# water.net
KiCad netlist of a schematic drawn in EAGLE
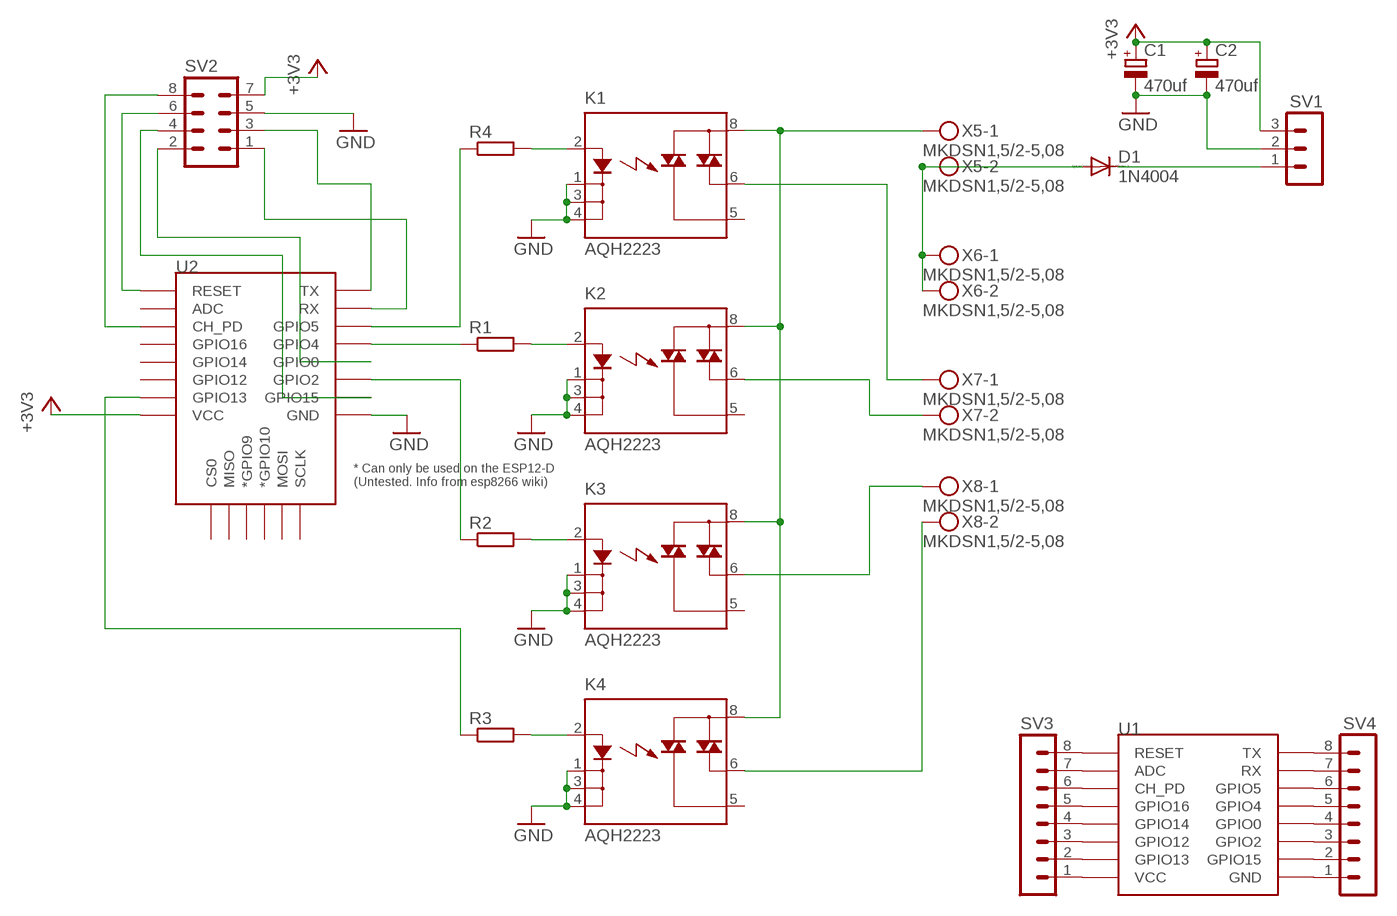
[diagram p0: schematic, sheet 1]

(export (version "E")
  (design (tool "Eeschema 10.0.6"))
  (components
    (comp (ref "C1")
      (value "470uf")
      (footprint "eagle-import:E5-10,5")
      (libsource (lib "eagle-import") (part "CPOL-EUE5-10.5"))
    )
    (comp (ref "C2")
      (value "470uf")
      (footprint "eagle-import:E5-10,5")
      (libsource (lib "eagle-import") (part "CPOL-EUE5-10.5"))
    )
    (comp (ref "D1")
      (value "1N4004")
      (footprint "eagle-import:DO41-10")
      (libsource (lib "eagle-import") (part "1N4004"))
    )
    (comp (ref "K1")
      (value "AQH2223")
      (footprint "eagle-import:DIL07")
      (fields (field (name "MF") "AROMAT/ MATSUSHITA"))
      (libsource (lib "eagle-import") (part "AQH2232"))
    )
    (comp (ref "K2")
      (value "AQH2223")
      (footprint "eagle-import:DIL07")
      (fields (field (name "MF") "AROMAT/ MATSUSHITA"))
      (libsource (lib "eagle-import") (part "AQH2232"))
    )
    (comp (ref "K3")
      (value "AQH2223")
      (footprint "eagle-import:DIL07")
      (fields (field (name "MF") "AROMAT/ MATSUSHITA"))
      (libsource (lib "eagle-import") (part "AQH2232"))
    )
    (comp (ref "K4")
      (value "AQH2223")
      (footprint "eagle-import:DIL07")
      (fields (field (name "MF") "AROMAT/ MATSUSHITA"))
      (libsource (lib "eagle-import") (part "AQH2232"))
    )
    (comp (ref "R1")
      (value "R-EU_R1206")
      (footprint "eagle-import:R1206")
      (libsource (lib "eagle-import") (part "R-EU_R1206"))
    )
    (comp (ref "R2")
      (value "R-EU_R1206")
      (footprint "eagle-import:R1206")
      (libsource (lib "eagle-import") (part "R-EU_R1206"))
    )
    (comp (ref "R3")
      (value "R-EU_R1206")
      (footprint "eagle-import:R1206")
      (libsource (lib "eagle-import") (part "R-EU_R1206"))
    )
    (comp (ref "R4")
      (value "R-EU_R1206")
      (footprint "eagle-import:R1206")
      (libsource (lib "eagle-import") (part "R-EU_R1206"))
    )
    (comp (ref "SV1")
      (value "MA03-1")
      (footprint "eagle-import:MA03-1")
      (libsource (lib "eagle-import") (part "MA03-1"))
    )
    (comp (ref "SV2")
      (value "MA04-2")
      (footprint "eagle-import:MA04-2")
      (libsource (lib "eagle-import") (part "MA04-2"))
    )
    (comp (ref "SV3")
      (value "MA08-1")
      (footprint "eagle-import:MA08-1")
      (libsource (lib "eagle-import") (part "MA08-1"))
    )
    (comp (ref "SV4")
      (value "MA08-1")
      (footprint "eagle-import:MA08-1")
      (libsource (lib "eagle-import") (part "MA08-1"))
    )
    (comp (ref "U1")
      (value "ESP12EPOGO")
      (footprint "eagle-import:ESP12E-POGO")
      (libsource (lib "eagle-import") (part "ESP12EPOGO"))
    )
    (comp (ref "U2")
      (value "ESP12ESMD")
      (footprint "eagle-import:ESP12E-SMD")
      (libsource (lib "eagle-import") (part "ESP12ESMD"))
    )
    (comp (ref "X5")
      (value "MKDSN1,5/2-5,08")
      (footprint "eagle-import:MKDSN1,5_2-5,08")
      (libsource (lib "eagle-import") (part "MKDSN1,5/2-5,08"))
    )
    (comp (ref "X6")
      (value "MKDSN1,5/2-5,08")
      (footprint "eagle-import:MKDSN1,5_2-5,08")
      (libsource (lib "eagle-import") (part "MKDSN1,5/2-5,08"))
    )
    (comp (ref "X7")
      (value "MKDSN1,5/2-5,08")
      (footprint "eagle-import:MKDSN1,5_2-5,08")
      (libsource (lib "eagle-import") (part "MKDSN1,5/2-5,08"))
    )
    (comp (ref "X8")
      (value "MKDSN1,5/2-5,08")
      (footprint "eagle-import:MKDSN1,5_2-5,08")
      (libsource (lib "eagle-import") (part "MKDSN1,5/2-5,08"))
    )
  )
  (nets
    (net (code "1") (name "+3V3") (class "Default")
      (node (ref "C1") (pin "+") (pinfunction "+_+") (pintype "passive"))
      (node (ref "C2") (pin "+") (pinfunction "+_+") (pintype "passive"))
      (node (ref "SV1") (pin "3") (pinfunction "3_3") (pintype "passive"))
      (node (ref "SV2") (pin "7") (pinfunction "7_7") (pintype "passive"))
      (node (ref "U2") (pin "VCC") (pinfunction "VCC_VCC") (pintype "bidirectional"))
    )
    (net (code "2") (name "GND") (class "Default")
      (node (ref "C1") (pin "-") (pinfunction "-_-") (pintype "passive"))
      (node (ref "C2") (pin "-") (pinfunction "-_-") (pintype "passive"))
      (node (ref "K1") (pin "1") (pinfunction "K_1") (pintype "passive"))
      (node (ref "K1") (pin "3") (pinfunction "K1_3") (pintype "passive"))
      (node (ref "K1") (pin "4") (pinfunction "K2_4") (pintype "passive"))
      (node (ref "K2") (pin "1") (pinfunction "K_1") (pintype "passive"))
      (node (ref "K2") (pin "3") (pinfunction "K1_3") (pintype "passive"))
      (node (ref "K2") (pin "4") (pinfunction "K2_4") (pintype "passive"))
      (node (ref "K3") (pin "1") (pinfunction "K_1") (pintype "passive"))
      (node (ref "K3") (pin "3") (pinfunction "K1_3") (pintype "passive"))
      (node (ref "K3") (pin "4") (pinfunction "K2_4") (pintype "passive"))
      (node (ref "K4") (pin "1") (pinfunction "K_1") (pintype "passive"))
      (node (ref "K4") (pin "3") (pinfunction "K1_3") (pintype "passive"))
      (node (ref "K4") (pin "4") (pinfunction "K2_4") (pintype "passive"))
      (node (ref "SV1") (pin "2") (pinfunction "2_2") (pintype "passive"))
      (node (ref "SV2") (pin "5") (pinfunction "5_5") (pintype "passive"))
      (node (ref "U2") (pin "GND") (pinfunction "GND_GND") (pintype "bidirectional"))
    )
    (net (code "3") (name "Net-(D1-PadC)") (class "Default")
      (node (ref "D1") (pin "C") (pinfunction "C_C") (pintype "passive"))
      (node (ref "SV1") (pin "1") (pinfunction "1_1") (pintype "passive"))
    )
    (net (code "4") (name "Net-(K1-A)") (class "Default")
      (node (ref "K1") (pin "2") (pinfunction "A_2") (pintype "passive"))
      (node (ref "R4") (pin "2") (pinfunction "2_2") (pintype "passive"))
    )
    (net (code "5") (name "Net-(K1-DS1)") (class "Default")
      (node (ref "K1") (pin "8") (pinfunction "DS1_8") (pintype "passive"))
      (node (ref "K2") (pin "8") (pinfunction "DS1_8") (pintype "passive"))
      (node (ref "K3") (pin "8") (pinfunction "DS1_8") (pintype "passive"))
      (node (ref "K4") (pin "8") (pinfunction "DS1_8") (pintype "passive"))
      (node (ref "X5") (pin "1") (pinfunction "KL_1") (pintype "passive"))
    )
    (net (code "6") (name "Net-(K1-DS3)") (class "Default")
      (node (ref "K1") (pin "6") (pinfunction "DS3_6") (pintype "passive"))
      (node (ref "X7") (pin "1") (pinfunction "KL_1") (pintype "passive"))
    )
    (net (code "7") (name "Net-(K2-A)") (class "Default")
      (node (ref "K2") (pin "2") (pinfunction "A_2") (pintype "passive"))
      (node (ref "R1") (pin "2") (pinfunction "2_2") (pintype "passive"))
    )
    (net (code "8") (name "Net-(K2-DS3)") (class "Default")
      (node (ref "K2") (pin "6") (pinfunction "DS3_6") (pintype "passive"))
      (node (ref "X7") (pin "2") (pinfunction "KL_2") (pintype "passive"))
    )
    (net (code "9") (name "Net-(K3-A)") (class "Default")
      (node (ref "K3") (pin "2") (pinfunction "A_2") (pintype "passive"))
      (node (ref "R2") (pin "2") (pinfunction "2_2") (pintype "passive"))
    )
    (net (code "10") (name "Net-(K3-DS3)") (class "Default")
      (node (ref "K3") (pin "6") (pinfunction "DS3_6") (pintype "passive"))
      (node (ref "X8") (pin "1") (pinfunction "KL_1") (pintype "passive"))
    )
    (net (code "11") (name "Net-(K4-A)") (class "Default")
      (node (ref "K4") (pin "2") (pinfunction "A_2") (pintype "passive"))
      (node (ref "R3") (pin "2") (pinfunction "2_2") (pintype "passive"))
    )
    (net (code "12") (name "Net-(K4-DS3)") (class "Default")
      (node (ref "K4") (pin "6") (pinfunction "DS3_6") (pintype "passive"))
      (node (ref "X8") (pin "2") (pinfunction "KL_2") (pintype "passive"))
    )
    (net (code "13") (name "Net-(R1-Pad1)") (class "Default")
      (node (ref "R1") (pin "1") (pinfunction "1_1") (pintype "passive"))
      (node (ref "U2") (pin "GPIO4") (pinfunction "GPIO4_GPIO4") (pintype "bidirectional"))
    )
    (net (code "14") (name "Net-(R2-Pad1)") (class "Default")
      (node (ref "R2") (pin "1") (pinfunction "1_1") (pintype "passive"))
      (node (ref "U2") (pin "GPIO2") (pinfunction "GPIO2_GPIO2") (pintype "bidirectional"))
    )
    (net (code "15") (name "Net-(R3-Pad1)") (class "Default")
      (node (ref "R3") (pin "1") (pinfunction "1_1") (pintype "passive"))
      (node (ref "U2") (pin "GPIO13") (pinfunction "GPIO13_GPIO13") (pintype "bidirectional"))
    )
    (net (code "16") (name "Net-(R4-Pad1)") (class "Default")
      (node (ref "R4") (pin "1") (pinfunction "1_1") (pintype "passive"))
      (node (ref "U2") (pin "GPIO5") (pinfunction "GPIO5_GPIO5") (pintype "bidirectional"))
    )
    (net (code "17") (name "Net-(SV2-Pad2)") (class "Default")
      (node (ref "SV2") (pin "2") (pinfunction "2_2") (pintype "passive"))
      (node (ref "U2") (pin "GPIO0") (pinfunction "GPIO0_GPIO0") (pintype "bidirectional"))
    )
    (net (code "18") (name "Net-(SV2-Pad4)") (class "Default")
      (node (ref "SV2") (pin "4") (pinfunction "4_4") (pintype "passive"))
      (node (ref "U2") (pin "GPIO15") (pinfunction "GPIO15_GPIO15") (pintype "bidirectional"))
    )
    (net (code "19") (name "Net-(SV2-Pad6)") (class "Default")
      (node (ref "SV2") (pin "6") (pinfunction "6_6") (pintype "passive"))
      (node (ref "U2") (pin "RESET") (pinfunction "RESET_RESET") (pintype "bidirectional"))
    )
    (net (code "20") (name "Net-(SV2-Pad8)") (class "Default")
      (node (ref "SV2") (pin "8") (pinfunction "8_8") (pintype "passive"))
      (node (ref "U2") (pin "CH_PD") (pinfunction "CH_PD_CH_PD") (pintype "bidirectional"))
    )
    (net (code "21") (name "Net-(SV3-Pad1)") (class "Default")
      (node (ref "SV3") (pin "1") (pinfunction "1_1") (pintype "passive"))
      (node (ref "U1") (pin "VCC") (pinfunction "VCC_VCC") (pintype "bidirectional"))
    )
    (net (code "22") (name "Net-(SV3-Pad2)") (class "Default")
      (node (ref "SV3") (pin "2") (pinfunction "2_2") (pintype "passive"))
      (node (ref "U1") (pin "GPIO13") (pinfunction "GPIO13_GPIO13") (pintype "bidirectional"))
    )
    (net (code "23") (name "Net-(SV3-Pad3)") (class "Default")
      (node (ref "SV3") (pin "3") (pinfunction "3_3") (pintype "passive"))
      (node (ref "U1") (pin "GPIO12") (pinfunction "GPIO12_GPIO12") (pintype "bidirectional"))
    )
    (net (code "24") (name "Net-(SV3-Pad4)") (class "Default")
      (node (ref "SV3") (pin "4") (pinfunction "4_4") (pintype "passive"))
      (node (ref "U1") (pin "GPIO14") (pinfunction "GPIO14_GPIO14") (pintype "bidirectional"))
    )
    (net (code "25") (name "Net-(SV3-Pad5)") (class "Default")
      (node (ref "SV3") (pin "5") (pinfunction "5_5") (pintype "passive"))
      (node (ref "U1") (pin "GPIO16") (pinfunction "GPIO16_GPIO16") (pintype "bidirectional"))
    )
    (net (code "26") (name "Net-(SV3-Pad6)") (class "Default")
      (node (ref "SV3") (pin "6") (pinfunction "6_6") (pintype "passive"))
      (node (ref "U1") (pin "CH_PD") (pinfunction "CH_PD_CH_PD") (pintype "bidirectional"))
    )
    (net (code "27") (name "Net-(SV3-Pad7)") (class "Default")
      (node (ref "SV3") (pin "7") (pinfunction "7_7") (pintype "passive"))
      (node (ref "U1") (pin "ADC") (pinfunction "ADC_ADC") (pintype "bidirectional"))
    )
    (net (code "28") (name "Net-(SV3-Pad8)") (class "Default")
      (node (ref "SV3") (pin "8") (pinfunction "8_8") (pintype "passive"))
      (node (ref "U1") (pin "RESET") (pinfunction "RESET_RESET") (pintype "bidirectional"))
    )
    (net (code "29") (name "Net-(SV4-Pad1)") (class "Default")
      (node (ref "SV4") (pin "1") (pinfunction "1_1") (pintype "passive"))
      (node (ref "U1") (pin "GND") (pinfunction "GND_GND") (pintype "bidirectional"))
    )
    (net (code "30") (name "Net-(SV4-Pad2)") (class "Default")
      (node (ref "SV4") (pin "2") (pinfunction "2_2") (pintype "passive"))
      (node (ref "U1") (pin "GPIO15") (pinfunction "GPIO15_GPIO15") (pintype "bidirectional"))
    )
    (net (code "31") (name "Net-(SV4-Pad3)") (class "Default")
      (node (ref "SV4") (pin "3") (pinfunction "3_3") (pintype "passive"))
      (node (ref "U1") (pin "GPIO2") (pinfunction "GPIO2_GPIO2") (pintype "bidirectional"))
    )
    (net (code "32") (name "Net-(SV4-Pad4)") (class "Default")
      (node (ref "SV4") (pin "4") (pinfunction "4_4") (pintype "passive"))
      (node (ref "U1") (pin "GPIO0") (pinfunction "GPIO0_GPIO0") (pintype "bidirectional"))
    )
    (net (code "33") (name "Net-(SV4-Pad5)") (class "Default")
      (node (ref "SV4") (pin "5") (pinfunction "5_5") (pintype "passive"))
      (node (ref "U1") (pin "GPIO4") (pinfunction "GPIO4_GPIO4") (pintype "bidirectional"))
    )
    (net (code "34") (name "Net-(SV4-Pad6)") (class "Default")
      (node (ref "SV4") (pin "6") (pinfunction "6_6") (pintype "passive"))
      (node (ref "U1") (pin "GPIO5") (pinfunction "GPIO5_GPIO5") (pintype "bidirectional"))
    )
    (net (code "35") (name "Net-(U1-RX)") (class "Default")
      (node (ref "SV4") (pin "7") (pinfunction "7_7") (pintype "passive"))
      (node (ref "U1") (pin "RXD0") (pinfunction "RX_RXD0") (pintype "bidirectional"))
    )
    (net (code "36") (name "Net-(U1-TX)") (class "Default")
      (node (ref "SV4") (pin "8") (pinfunction "8_8") (pintype "passive"))
      (node (ref "U1") (pin "TXD0") (pinfunction "TX_TXD0") (pintype "bidirectional"))
    )
    (net (code "37") (name "Net-(U2-RX)") (class "Default")
      (node (ref "SV2") (pin "1") (pinfunction "1_1") (pintype "passive"))
      (node (ref "U2") (pin "RXD0") (pinfunction "RX_RXD0") (pintype "bidirectional"))
    )
    (net (code "38") (name "Net-(U2-TX)") (class "Default")
      (node (ref "SV2") (pin "3") (pinfunction "3_3") (pintype "passive"))
      (node (ref "U2") (pin "TXD0") (pinfunction "TX_TXD0") (pintype "bidirectional"))
    )
    (net (code "39") (name "Net-(X5B-KL)") (class "Default")
      (node (ref "D1") (pin "A") (pinfunction "A_A") (pintype "passive"))
      (node (ref "X5") (pin "2") (pinfunction "KL_2") (pintype "passive"))
      (node (ref "X6") (pin "1") (pinfunction "KL_1") (pintype "passive"))
      (node (ref "X6") (pin "2") (pinfunction "KL_2") (pintype "passive"))
    )
    (net (code "40") (name "unconnected-(K1-DS2-Pad5)") (class "Default")
      (node (ref "K1") (pin "5") (pinfunction "DS2_5") (pintype "passive"))
    )
    (net (code "41") (name "unconnected-(K2-DS2-Pad5)") (class "Default")
      (node (ref "K2") (pin "5") (pinfunction "DS2_5") (pintype "passive"))
    )
    (net (code "42") (name "unconnected-(K3-DS2-Pad5)") (class "Default")
      (node (ref "K3") (pin "5") (pinfunction "DS2_5") (pintype "passive"))
    )
    (net (code "43") (name "unconnected-(K4-DS2-Pad5)") (class "Default")
      (node (ref "K4") (pin "5") (pinfunction "DS2_5") (pintype "passive"))
    )
    (net (code "44") (name "unconnected-(U2-*GPIO9-PadGPIO9)") (class "Default")
      (node (ref "U2") (pin "GPIO9") (pinfunction "*GPIO9_GPIO9") (pintype "bidirectional"))
    )
    (net (code "45") (name "unconnected-(U2-*GPIO10-PadGPIO10)") (class "Default")
      (node (ref "U2") (pin "GPIO10") (pinfunction "*GPIO10_GPIO10") (pintype "bidirectional"))
    )
    (net (code "46") (name "unconnected-(U2-PadADC)") (class "Default")
      (node (ref "U2") (pin "ADC") (pinfunction "ADC_ADC") (pintype "bidirectional"))
    )
    (net (code "47") (name "unconnected-(U2-PadCS0)") (class "Default")
      (node (ref "U2") (pin "CS0") (pinfunction "CS0_CS0") (pintype "bidirectional"))
    )
    (net (code "48") (name "unconnected-(U2-PadGPIO12)") (class "Default")
      (node (ref "U2") (pin "GPIO12") (pinfunction "GPIO12_GPIO12") (pintype "bidirectional"))
    )
    (net (code "49") (name "unconnected-(U2-PadGPIO14)") (class "Default")
      (node (ref "U2") (pin "GPIO14") (pinfunction "GPIO14_GPIO14") (pintype "bidirectional"))
    )
    (net (code "50") (name "unconnected-(U2-PadGPIO16)") (class "Default")
      (node (ref "U2") (pin "GPIO16") (pinfunction "GPIO16_GPIO16") (pintype "bidirectional"))
    )
    (net (code "51") (name "unconnected-(U2-PadMISO)") (class "Default")
      (node (ref "U2") (pin "MISO") (pinfunction "MISO_MISO") (pintype "bidirectional"))
    )
    (net (code "52") (name "unconnected-(U2-PadMOSI)") (class "Default")
      (node (ref "U2") (pin "MOSI") (pinfunction "MOSI_MOSI") (pintype "bidirectional"))
    )
    (net (code "53") (name "unconnected-(U2-PadSCLK)") (class "Default")
      (node (ref "U2") (pin "SCLK") (pinfunction "SCLK_SCLK") (pintype "bidirectional"))
    )
  )
)
